# Uart.net
KiCad netlist of a schematic drawn in Altium Designer
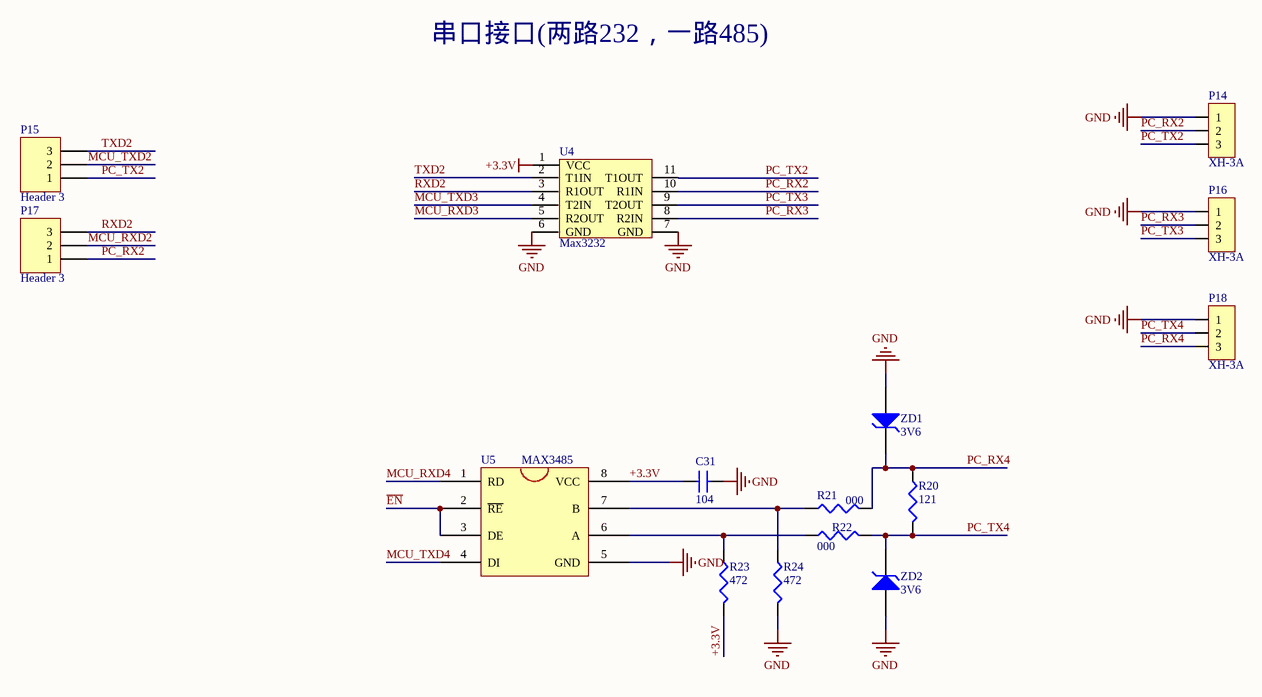
[diagram p0: Uart.SchDoc]

(export (version "E")
  (design (tool "Eeschema 10.0.6"))
  (components
    (comp (ref "C31")
      (value "104")
      (footprint "0603C")
      (description "Capacitor")
      (libsource (lib "*") (part "电容"))
    )
    (comp (ref "P14")
      (value "XH-3A")
      (footprint "CN3-2.54")
      (description "CONN,XH-3A,3PIN,2.54mm插座")
      (libsource (lib "SR SCH Library V02") (part "CONN-XH-3A"))
    )
    (comp (ref "P15")
      (value "Header 3")
      (footprint "HDR1X3")
      (description "Header, 3-Pin")
      (fields (field (name "PUBLISHER") "Altium Limited"))
      (libsource (lib "Miscellaneous Connectors") (part "Header 3"))
    )
    (comp (ref "P16")
      (value "XH-3A")
      (footprint "CN3-2.54")
      (description "CONN,XH-3A,3PIN,2.54mm插座")
      (libsource (lib "SR SCH Library V02") (part "CONN-XH-3A"))
    )
    (comp (ref "P17")
      (value "Header 3")
      (footprint "HDR1X3")
      (description "Header, 3-Pin")
      (fields (field (name "PUBLISHER") "Altium Limited"))
      (libsource (lib "Miscellaneous Connectors") (part "Header 3"))
    )
    (comp (ref "P18")
      (value "XH-3A")
      (footprint "CN3-2.54")
      (description "CONN,XH-3A,3PIN,2.54mm插座")
      (libsource (lib "SR SCH Library V02") (part "CONN-XH-3A"))
    )
    (comp (ref "R20") (value "121") (footprint "0603R") (libsource (lib "*") (part "RES1")))
    (comp (ref "R21") (value "000") (footprint "0603R") (libsource (lib "*") (part "RES1")))
    (comp (ref "R22") (value "000") (footprint "0603R") (libsource (lib "*") (part "RES1")))
    (comp (ref "R23") (value "472") (footprint "0603R") (libsource (lib "*") (part "RES1")))
    (comp (ref "R24") (value "472") (footprint "0603R") (libsource (lib "*") (part "RES1")))
    (comp (ref "U4")
      (value "Max3232")
      (footprint "Community V01")
      (libsource (lib "SR SCH Library V02") (part "Community V01"))
    )
    (comp (ref "U5") (value "MAX3485") (footprint "SOP8") (libsource (lib "其他常用器件") (part "MAX485")))
    (comp (ref "ZD1")
      (value "3V6")
      (footprint "SMA For SML4729A")
      (description "constant diode")
      (libsource (lib "其他常用器件") (part "稳压二极管"))
    )
    (comp (ref "ZD2")
      (value "3V6")
      (footprint "SMA For SML4729A")
      (description "constant diode")
      (libsource (lib "其他常用器件") (part "稳压二极管"))
    )
  )
  (nets
    (net (code "1") (name "+3.3V") (class "Default")
      (node (ref "C31") (pin "1") (pinfunction "1_1") (pintype "passive"))
      (node (ref "R23") (pin "2") (pinfunction "2_2") (pintype "passive"))
      (node (ref "U4") (pin "1") (pinfunction "VCC_1") (pintype "passive"))
      (node (ref "U5") (pin "8") (pinfunction "VCC_8") (pintype "passive"))
    )
    (net (code "2") (name "/MCU_RXD2") (class "Default")
      (node (ref "P17") (pin "2") (pinfunction "2_2") (pintype "passive"))
    )
    (net (code "3") (name "/MCU_RXD3") (class "Default")
      (node (ref "U4") (pin "5") (pinfunction "R2OUT_5") (pintype "passive"))
    )
    (net (code "4") (name "/MCU_RXD4") (class "Default")
      (node (ref "U5") (pin "1") (pinfunction "RD_1") (pintype "passive"))
    )
    (net (code "5") (name "/MCU_TXD2") (class "Default")
      (node (ref "P15") (pin "2") (pinfunction "2_2") (pintype "passive"))
    )
    (net (code "6") (name "/MCU_TXD3") (class "Default")
      (node (ref "U4") (pin "4") (pinfunction "T2IN_4") (pintype "passive"))
    )
    (net (code "7") (name "/MCU_TXD4") (class "Default")
      (node (ref "U5") (pin "4") (pinfunction "DI_4") (pintype "passive"))
    )
    (net (code "8") (name "/PC_RX2") (class "Default")
      (node (ref "P14") (pin "2") (pinfunction "2_2") (pintype "passive"))
      (node (ref "P17") (pin "1") (pinfunction "1_1") (pintype "passive"))
      (node (ref "U4") (pin "10") (pinfunction "R1IN_10") (pintype "passive"))
    )
    (net (code "9") (name "/PC_RX3") (class "Default")
      (node (ref "P16") (pin "2") (pinfunction "2_2") (pintype "passive"))
      (node (ref "U4") (pin "8") (pinfunction "R2IN_8") (pintype "passive"))
    )
    (net (code "10") (name "/PC_RX4") (class "Default")
      (node (ref "P18") (pin "3") (pinfunction "3_3") (pintype "passive"))
      (node (ref "R20") (pin "1") (pinfunction "1_1") (pintype "passive"))
      (node (ref "R21") (pin "2") (pinfunction "2_2") (pintype "passive"))
      (node (ref "ZD1") (pin "2") (pinfunction "2_2") (pintype "passive"))
    )
    (net (code "11") (name "/PC_TX2") (class "Default")
      (node (ref "P14") (pin "3") (pinfunction "3_3") (pintype "passive"))
      (node (ref "P15") (pin "1") (pinfunction "1_1") (pintype "passive"))
      (node (ref "U4") (pin "11") (pinfunction "T1OUT_11") (pintype "passive"))
    )
    (net (code "12") (name "/PC_TX3") (class "Default")
      (node (ref "P16") (pin "3") (pinfunction "3_3") (pintype "passive"))
      (node (ref "U4") (pin "9") (pinfunction "T2OUT_9") (pintype "passive"))
    )
    (net (code "13") (name "/PC_TX4") (class "Default")
      (node (ref "P18") (pin "2") (pinfunction "2_2") (pintype "passive"))
      (node (ref "R20") (pin "2") (pinfunction "2_2") (pintype "passive"))
      (node (ref "R22") (pin "2") (pinfunction "2_2") (pintype "passive"))
      (node (ref "ZD2") (pin "2") (pinfunction "2_2") (pintype "passive"))
    )
    (net (code "14") (name "/RXD2") (class "Default")
      (node (ref "P17") (pin "3") (pinfunction "3_3") (pintype "passive"))
      (node (ref "U4") (pin "3") (pinfunction "R1OUT_3") (pintype "passive"))
    )
    (net (code "15") (name "/TXD2") (class "Default")
      (node (ref "P15") (pin "3") (pinfunction "3_3") (pintype "passive"))
      (node (ref "U4") (pin "2") (pinfunction "T1IN_2") (pintype "passive"))
    )
    (net (code "16") (name "/~{EN}") (class "Default")
      (node (ref "U5") (pin "2") (pinfunction "~{RE}_2") (pintype "passive"))
      (node (ref "U5") (pin "3") (pinfunction "DE_3") (pintype "passive"))
    )
    (net (code "17") (name "GND") (class "Default")
      (node (ref "C31") (pin "2") (pinfunction "2_2") (pintype "passive"))
      (node (ref "P14") (pin "1") (pinfunction "1_1") (pintype "passive"))
      (node (ref "P16") (pin "1") (pinfunction "1_1") (pintype "passive"))
      (node (ref "P18") (pin "1") (pinfunction "1_1") (pintype "passive"))
      (node (ref "R24") (pin "2") (pinfunction "2_2") (pintype "passive"))
      (node (ref "U4") (pin "6") (pinfunction "GND_6") (pintype "passive"))
      (node (ref "U4") (pin "7") (pinfunction "GND_7") (pintype "passive"))
      (node (ref "U5") (pin "5") (pinfunction "GND_5") (pintype "passive"))
      (node (ref "ZD1") (pin "1") (pinfunction "1_1") (pintype "passive"))
      (node (ref "ZD2") (pin "1") (pinfunction "1_1") (pintype "passive"))
    )
    (net (code "18") (name "Net-(U5-A)") (class "Default")
      (node (ref "R22") (pin "1") (pinfunction "1_1") (pintype "passive"))
      (node (ref "R23") (pin "1") (pinfunction "1_1") (pintype "passive"))
      (node (ref "U5") (pin "6") (pinfunction "A_6") (pintype "passive"))
    )
    (net (code "19") (name "Net-(U5-B)") (class "Default")
      (node (ref "R21") (pin "1") (pinfunction "1_1") (pintype "passive"))
      (node (ref "R24") (pin "1") (pinfunction "1_1") (pintype "passive"))
      (node (ref "U5") (pin "7") (pinfunction "B_7") (pintype "passive"))
    )
  )
)
